# Sheet1_v12.net
KiCad netlist of a schematic drawn in Altium Designer
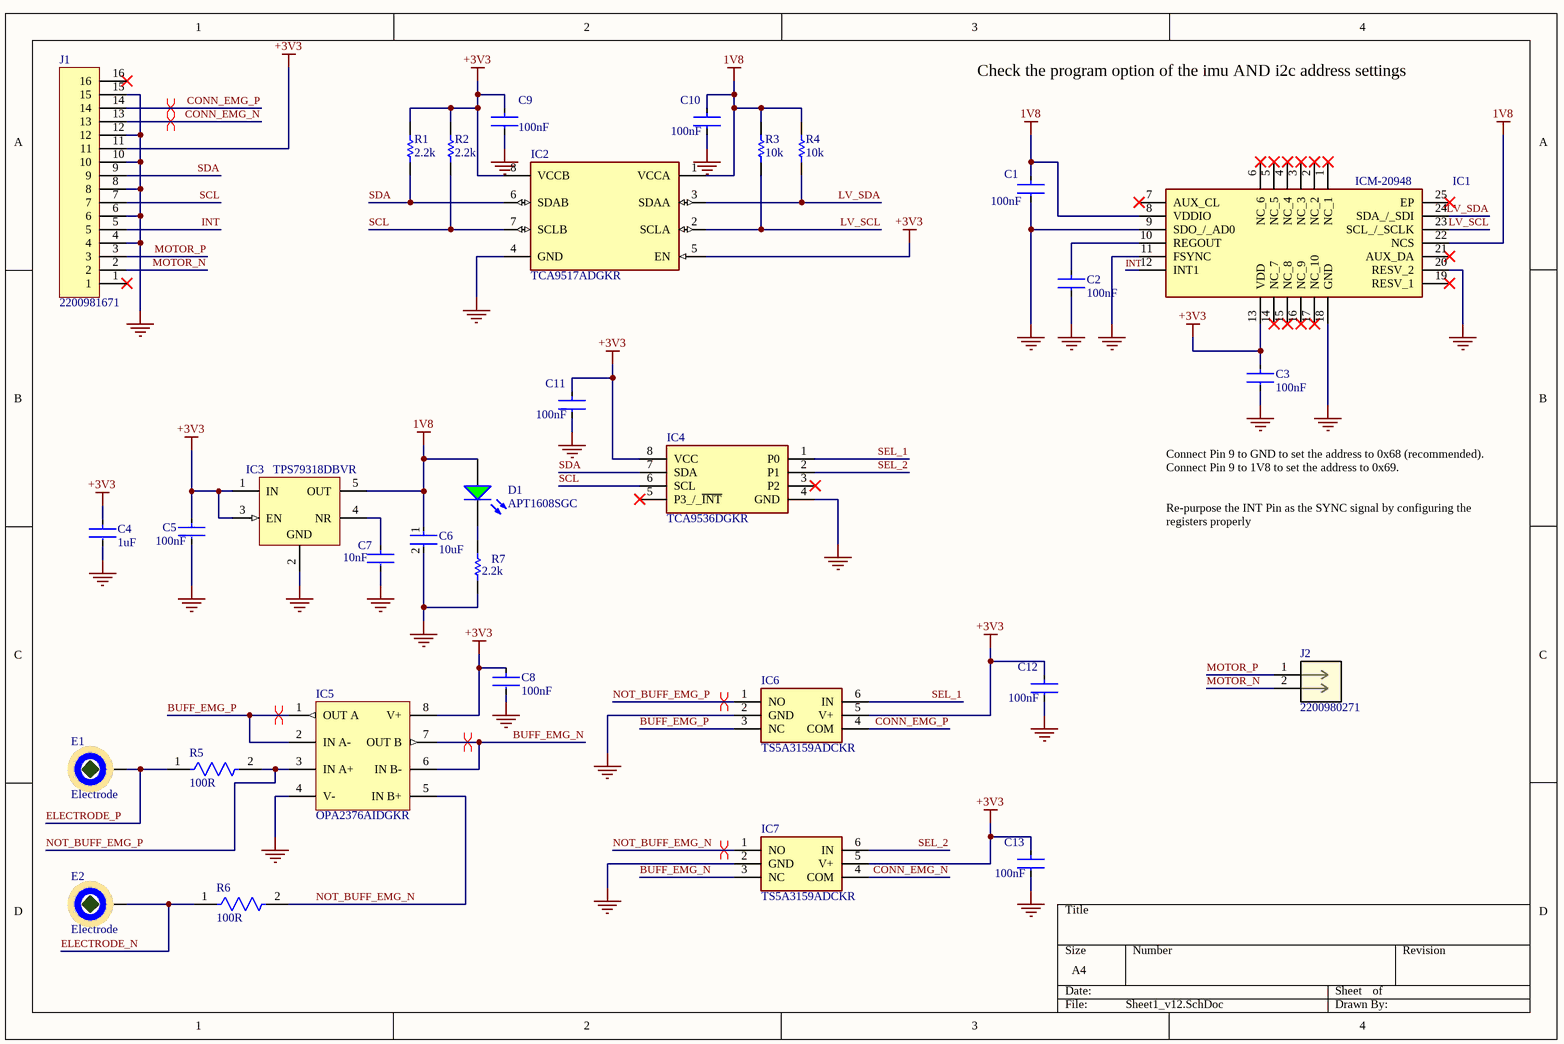
[diagram p0: Sheet1_v12.SchDoc]

(export (version "E")
  (design (tool "Eeschema 10.0.6"))
  (components
    (comp (ref "C1")
      (value "100nF")
      (footprint "FP-CC0603-DA-MFG")
      (description "100nF 50V X7R ±10% 0603 Multilayer Ceramic Capacitors MLCC - SMD/SMT ROHS")
      (fields (field (name "MANUFACTURER") "YAGEO") (field (name "VOLTAGE") "50 V"))
      (libsource (lib "Altium Content Vault") (part "11868f565c42a9108669ba33697ecf6"))
    )
    (comp (ref "C2")
      (value "100nF")
      (footprint "FP-CC0603-DA-MFG")
      (description "100nF 50V X7R ±10% 0603 Multilayer Ceramic Capacitors MLCC - SMD/SMT ROHS")
      (fields (field (name "MANUFACTURER") "YAGEO") (field (name "VOLTAGE") "50 V"))
      (libsource (lib "Altium Content Vault") (part "11868f565c42a9108669ba33697ecf6"))
    )
    (comp (ref "C3")
      (value "100nF")
      (footprint "FP-CC0603-DA-MFG")
      (description "100nF 50V X7R ±10% 0603 Multilayer Ceramic Capacitors MLCC - SMD/SMT ROHS")
      (fields (field (name "MANUFACTURER") "YAGEO") (field (name "VOLTAGE") "50 V"))
      (libsource (lib "Altium Content Vault") (part "11868f565c42a9108669ba33697ecf6"))
    )
    (comp (ref "C4")
      (value "1uF")
      (footprint "FP-C0402C-BB-IPC_B")
      (description "CAP CER 1UF 16V X5R 0402")
      (fields (field (name "TOLERANCE") "10%") (field (name "MPN") "C0402C105K4PACTU"))
      (libsource (lib "") (part "b4654b650e69147ec39a6b967a45e02_1"))
    )
    (comp (ref "C5")
      (value "100nF")
      (footprint "FP-GRM155-0_05-MFG")
      (description "Chip Multilayer Ceramic Capacitors for General Purpose, 0402, 0.10uF, X7S, 22%, 10%, 50V")
      (fields (field (name "TOLERANCE") "10%") (field (name "MPN") "GRM155C71H104KE19D"))
      (libsource (lib "Altium Content Vault") (part "02cd4be3c70576c341d710602a673aa"))
    )
    (comp (ref "C6")
      (value "10uF")
      (footprint "FP-GRM155-0_2-IPC_A")
      (description "Chip Multilayer Ceramic Capacitors for General Purpose, 0402, 10uF, X5R, 15%, 20%, 10V")
      (fields (field (name "MPN") "GRM155R61A106ME11D"))
      (libsource (lib "Altium Content Vault") (part "b4654b650e69147ec39a6b967a45e02"))
    )
    (comp (ref "C7")
      (value "10nF")
      (footprint "FP-C0402-BB-MFG")
      (description "C0402 10,000 pF X7R 10.00% 50 V")
      (fields
        (field (name "OCTOPART") "https://octopart.com/c0402c103k5rac7411-kemet-25528449")
        (field (name "TOLERANCE") "0.1")
      )
      (libsource (lib "") (part "b4654b650e69147ec39a6b967a45e02_1"))
    )
    (comp (ref "C8")
      (value "100nF")
      (footprint "FP-CC0603-DA-MFG")
      (description "100nF 50V X7R ±10% 0603 Multilayer Ceramic Capacitors MLCC - SMD/SMT ROHS")
      (fields (field (name "MANUFACTURER") "YAGEO") (field (name "VOLTAGE") "50 V"))
      (libsource (lib "Altium Content Vault") (part "11868f565c42a9108669ba33697ecf6"))
    )
    (comp (ref "C9")
      (value "100nF")
      (footprint "FP-GRM155-0_05-MFG")
      (description "Chip Multilayer Ceramic Capacitors for General Purpose, 0402, 0.10uF, X7S, 22%, 10%, 50V")
      (fields (field (name "TOLERANCE") "10%") (field (name "MPN") "GRM155C71H104KE19D"))
      (libsource (lib "Altium Content Vault") (part "02cd4be3c70576c341d710602a673aa"))
    )
    (comp (ref "C10")
      (value "100nF")
      (footprint "FP-GRM155-0_05-MFG")
      (description "Chip Multilayer Ceramic Capacitors for General Purpose, 0402, 0.10uF, X7S, 22%, 10%, 50V")
      (fields (field (name "TOLERANCE") "10%") (field (name "MPN") "GRM155C71H104KE19D"))
      (libsource (lib "Altium Content Vault") (part "02cd4be3c70576c341d710602a673aa"))
    )
    (comp (ref "C11")
      (value "100nF")
      (footprint "FP-GRM155-0_05-MFG")
      (description "Chip Multilayer Ceramic Capacitors for General Purpose, 0402, 0.10uF, X7S, 22%, 10%, 50V")
      (fields (field (name "TOLERANCE") "10%") (field (name "MPN") "GRM155C71H104KE19D"))
      (libsource (lib "Altium Content Vault") (part "02cd4be3c70576c341d710602a673aa"))
    )
    (comp (ref "C12")
      (value "100nF")
      (footprint "FP-GRM155-0_05-MFG")
      (description "Chip Multilayer Ceramic Capacitors for General Purpose, 0402, 0.10uF, X7S, 22%, 10%, 50V")
      (fields (field (name "TOLERANCE") "10%") (field (name "MPN") "GRM155C71H104KE19D"))
      (libsource (lib "Altium Content Vault") (part "02cd4be3c70576c341d710602a673aa"))
    )
    (comp (ref "C13")
      (value "100nF")
      (footprint "FP-GRM155-0_05-MFG")
      (description "Chip Multilayer Ceramic Capacitors for General Purpose, 0402, 0.10uF, X7S, 22%, 10%, 50V")
      (fields (field (name "TOLERANCE") "10%") (field (name "MPN") "GRM155C71H104KE19D"))
      (libsource (lib "Altium Content Vault") (part "02cd4be3c70576c341d710602a673aa"))
    )
    (comp (ref "D1")
      (value "APT1608SGC")
      (footprint "KING-APT1608SGC_V")
      (description "Super Bright Green LED, 62.5 mW, 25 mA, -40 to 85 degC, 2-Pin SMD, RoHS, Tape and Reel")
      (fields (field (name "MANUFACTURER") "Kingbright"))
      (libsource (lib "Altium Content Vault") (part "LED-GREEN-AK-2"))
    )
    (comp (ref "E1")
      (value "Electrode")
      (footprint "Electrode")
      (libsource (lib "Sensor_node") (part "Electrode"))
    )
    (comp (ref "E2")
      (value "Electrode")
      (footprint "Electrode")
      (libsource (lib "Sensor_node") (part "Electrode"))
    )
    (comp (ref "IC1")
      (value "ICM-20948")
      (footprint "SamacSys:QFN40P300X300X105-25N-D")
      (description "Integrated Circuit")
      (fields (field (name "MOUSER PART NUMBER") "410-ICM-20948"))
      (libsource (lib "*") (part "ICM-20948"))
    )
    (comp (ref "IC2")
      (value "TCA9517ADGKR")
      (footprint "FP-DGK0008A-IPC_C")
      (description "IC TRNSLTR BIDIRECTIONAL 8VSSOP")
      (libsource (lib "Altium Content Vault") (part "376f503177af6135b4bcb823927ec01"))
    )
    (comp (ref "IC3")
      (value "TPS79318DBVR")
      (footprint "DBV0005A_M")
      (fields (field (name "MANUFACTURER") "Texas Instruments"))
      (libsource (lib "Altium Content Vault") (part "TI-TPS79NXX-YYSOT5"))
    )
    (comp (ref "IC4")
      (value "TCA9536DGKR")
      (footprint "SamacSys:SOP65P490X110-8N")
      (description "Integrated Circuit")
      (fields (field (name "MOUSER PART NUMBER") "595-TCA9536DGKR"))
      (libsource (lib "*") (part "TCA9536DGKR"))
    )
    (comp (ref "IC5")
      (value "OPA2376AIDGKR")
      (footprint "OPA2376")
      (description "IC OPAMP GP 2 CIRCUIT 8VSSOP")
      (libsource (lib "Sensor_node") (part "OPA2376AIDGKR"))
    )
    (comp (ref "IC6")
      (value "TS5A3159ADCKR")
      (footprint "SamacSys:SOT65P210X110-6N")
      (description "IC SWITCH SPDTX1 900MOHM SC70-6")
      (fields (field (name "MOUSER PART NUMBER") "595-TS5A3159ADCKR"))
      (libsource (lib "*") (part "TS5A3159ADCKR"))
    )
    (comp (ref "IC7")
      (value "TS5A3159ADCKR")
      (footprint "SamacSys:SOT65P210X110-6N")
      (description "IC SWITCH SPDTX1 900MOHM SC70-6")
      (fields (field (name "MOUSER PART NUMBER") "595-TS5A3159ADCKR"))
      (libsource (lib "*") (part "TS5A3159ADCKR"))
    )
    (comp (ref "J1")
      (value "2200981671")
      (footprint "CONN_2200980000-SD_16_MOL")
      (description "Connector Header Through Hole, Right Angle 16 position 0.049\" (1.25mm)")
      (libsource (lib "Sensor_node") (part "2200981671"))
    )
    (comp (ref "J2")
      (value "2200980271")
      (footprint "2X1_right_angle_THT_CON")
      (description "Molex connector")
      (libsource (lib "Sensor_node") (part "2X1_RHTANG_HDR"))
    )
    (comp (ref "R1")
      (value "2.2k")
      (footprint "RESC0402(1005)_N")
      (description "2K2 0.063W 5% 0402 (1005 Metric)  SMD")
      (fields (field (name "TOLERANCE") "5 %") (field (name "POWER") "0.063 W"))
      (libsource (lib "Altium Content Vault") (part "RES"))
    )
    (comp (ref "R2")
      (value "2.2k")
      (footprint "RESC0402(1005)_N")
      (description "2K2 0.063W 5% 0402 (1005 Metric)  SMD")
      (fields (field (name "TOLERANCE") "5 %") (field (name "POWER") "0.063 W"))
      (libsource (lib "Altium Content Vault") (part "RES"))
    )
    (comp (ref "R3")
      (value "10k")
      (footprint "RESC1005X40X20NL05T10")
      (fields
        (field (name "MANUFACTURER") "Vishay BCcomponents")
        (field (name "PART NUMBER") "TNPW040210K0DEED")
      )
      (libsource (lib "Altium Content Vault") (part "RES"))
    )
    (comp (ref "R4")
      (value "10k")
      (footprint "RESC1005X40X20NL05T10")
      (fields
        (field (name "MANUFACTURER") "Vishay BCcomponents")
        (field (name "PART NUMBER") "TNPW040210K0DEED")
      )
      (libsource (lib "Altium Content Vault") (part "RES"))
    )
    (comp (ref "R5")
      (value "100R")
      (footprint "FP-MCS0402-IPC_B")
      (description "RES SMD 1.2K OHM 1% 1/10W 0402")
      (fields (field (name "TOLERANCE") "0.5%") (field (name "MPN") "MCS0402MD1000DE000"))
      (libsource (lib "Altium Content Vault") (part "1029c3af85768c4190bb7ad29bc67b5"))
    )
    (comp (ref "R6")
      (value "100R")
      (footprint "FP-MCS0402-IPC_B")
      (description "RES SMD 1.2K OHM 1% 1/10W 0402")
      (fields (field (name "TOLERANCE") "0.5%") (field (name "MPN") "MCS0402MD1000DE000"))
      (libsource (lib "Altium Content Vault") (part "1029c3af85768c4190bb7ad29bc67b5"))
    )
    (comp (ref "R7")
      (value "2.2k")
      (footprint "RESC0402(1005)_N")
      (description "2K2 0.063W 5% 0402 (1005 Metric)  SMD")
      (fields (field (name "TOLERANCE") "5 %") (field (name "POWER") "0.063 W"))
      (libsource (lib "Altium Content Vault") (part "RES"))
    )
  )
  (nets
    (net (code "1") (name "+3V3") (class "Default")
      (node (ref "C11") (pin "1") (pinfunction "1_1") (pintype "passive"))
      (node (ref "C12") (pin "1") (pinfunction "1_1") (pintype "passive"))
      (node (ref "C13") (pin "1") (pinfunction "1_1") (pintype "passive"))
      (node (ref "C3") (pin "1") (pinfunction "1_1") (pintype "passive"))
      (node (ref "C4") (pin "1") (pinfunction "1_1") (pintype "passive"))
      (node (ref "C5") (pin "1") (pinfunction "1_1") (pintype "passive"))
      (node (ref "C8") (pin "1") (pinfunction "1_1") (pintype "passive"))
      (node (ref "C9") (pin "1") (pinfunction "1_1") (pintype "passive"))
      (node (ref "IC1") (pin "13") (pinfunction "VDD_13") (pintype "passive"))
      (node (ref "IC2") (pin "5") (pinfunction "EN_5") (pintype "input"))
      (node (ref "IC2") (pin "8") (pinfunction "VCCB_8") (pintype "power_in"))
      (node (ref "IC3") (pin "1") (pinfunction "IN_1") (pintype "power_in"))
      (node (ref "IC3") (pin "3") (pinfunction "EN_3") (pintype "input"))
      (node (ref "IC4") (pin "8") (pinfunction "VCC_8") (pintype "passive"))
      (node (ref "IC5") (pin "8") (pinfunction "V+_8") (pintype "power_in"))
      (node (ref "IC6") (pin "5") (pinfunction "V+_5") (pintype "passive"))
      (node (ref "IC7") (pin "5") (pinfunction "V+_5") (pintype "passive"))
      (node (ref "J1") (pin "11") (pinfunction "11_11") (pintype "passive"))
      (node (ref "R1") (pin "2") (pinfunction "2_2") (pintype "passive"))
      (node (ref "R2") (pin "2") (pinfunction "2_2") (pintype "passive"))
    )
    (net (code "2") (name "/BUFF_EMG_N") (class "Default")
      (node (ref "IC5") (pin "6") (pinfunction "IN_B-_6") (pintype "passive"))
      (node (ref "IC5") (pin "7") (pinfunction "OUT_B_7") (pintype "output"))
      (node (ref "IC7") (pin "3") (pinfunction "NC_3") (pintype "passive"))
    )
    (net (code "3") (name "/BUFF_EMG_P") (class "Default")
      (node (ref "IC5") (pin "1") (pinfunction "OUT_A_1") (pintype "output"))
      (node (ref "IC5") (pin "2") (pinfunction "IN_A-_2") (pintype "passive"))
      (node (ref "IC6") (pin "3") (pinfunction "NC_3") (pintype "passive"))
    )
    (net (code "4") (name "/CONN_EMG_N") (class "Default")
      (node (ref "IC7") (pin "4") (pinfunction "COM_4") (pintype "passive"))
      (node (ref "J1") (pin "13") (pinfunction "13_13") (pintype "passive"))
    )
    (net (code "5") (name "/CONN_EMG_P") (class "Default")
      (node (ref "IC6") (pin "4") (pinfunction "COM_4") (pintype "passive"))
      (node (ref "J1") (pin "14") (pinfunction "14_14") (pintype "passive"))
    )
    (net (code "6") (name "/ELECTRODE_N") (class "Default")
      (node (ref "E2") (pin "1") (pinfunction "1_1") (pintype "passive"))
      (node (ref "R6") (pin "1") (pinfunction "1_1") (pintype "passive"))
    )
    (net (code "7") (name "/ELECTRODE_P") (class "Default")
      (node (ref "E1") (pin "1") (pinfunction "1_1") (pintype "passive"))
      (node (ref "R5") (pin "1") (pinfunction "1_1") (pintype "passive"))
    )
    (net (code "8") (name "/INT") (class "Default")
      (node (ref "IC1") (pin "12") (pinfunction "INT1_12") (pintype "passive"))
      (node (ref "J1") (pin "5") (pinfunction "5_5") (pintype "passive"))
    )
    (net (code "9") (name "/LV_SCL") (class "Default")
      (node (ref "IC1") (pin "23") (pinfunction "SCL_/_SCLK_23") (pintype "passive"))
      (node (ref "IC2") (pin "2") (pinfunction "SCLA_2") (pintype "bidirectional"))
      (node (ref "R3") (pin "1") (pinfunction "1_1") (pintype "passive"))
    )
    (net (code "10") (name "/LV_SDA") (class "Default")
      (node (ref "IC1") (pin "24") (pinfunction "SDA_/_SDI_24") (pintype "passive"))
      (node (ref "IC2") (pin "3") (pinfunction "SDAA_3") (pintype "bidirectional"))
      (node (ref "R4") (pin "1") (pinfunction "1_1") (pintype "passive"))
    )
    (net (code "11") (name "/MOTOR_N") (class "Default")
      (node (ref "J1") (pin "2") (pinfunction "2_2") (pintype "passive"))
      (node (ref "J2") (pin "2") (pinfunction "2_2") (pintype "passive"))
    )
    (net (code "12") (name "/MOTOR_P") (class "Default")
      (node (ref "J1") (pin "3") (pinfunction "3_3") (pintype "passive"))
      (node (ref "J2") (pin "1") (pinfunction "1_1") (pintype "passive"))
    )
    (net (code "13") (name "/NOT_BUFF_EMG_N") (class "Default")
      (node (ref "IC5") (pin "5") (pinfunction "IN_B+_5") (pintype "passive"))
      (node (ref "IC7") (pin "1") (pinfunction "NO_1") (pintype "passive"))
      (node (ref "R6") (pin "2") (pinfunction "2_2") (pintype "passive"))
    )
    (net (code "14") (name "/NOT_BUFF_EMG_P") (class "Default")
      (node (ref "IC5") (pin "3") (pinfunction "IN_A+_3") (pintype "passive"))
      (node (ref "IC6") (pin "1") (pinfunction "NO_1") (pintype "passive"))
      (node (ref "R5") (pin "2") (pinfunction "2_2") (pintype "passive"))
    )
    (net (code "15") (name "/SCL") (class "Default")
      (node (ref "IC2") (pin "7") (pinfunction "SCLB_7") (pintype "bidirectional"))
      (node (ref "IC4") (pin "6") (pinfunction "SCL_6") (pintype "passive"))
      (node (ref "J1") (pin "7") (pinfunction "7_7") (pintype "passive"))
      (node (ref "R2") (pin "1") (pinfunction "1_1") (pintype "passive"))
    )
    (net (code "16") (name "/SDA") (class "Default")
      (node (ref "IC2") (pin "6") (pinfunction "SDAB_6") (pintype "bidirectional"))
      (node (ref "IC4") (pin "7") (pinfunction "SDA_7") (pintype "passive"))
      (node (ref "J1") (pin "9") (pinfunction "9_9") (pintype "passive"))
      (node (ref "R1") (pin "1") (pinfunction "1_1") (pintype "passive"))
    )
    (net (code "17") (name "/SEL_1") (class "Default")
      (node (ref "IC4") (pin "1") (pinfunction "P0_1") (pintype "passive"))
      (node (ref "IC6") (pin "6") (pinfunction "IN_6") (pintype "passive"))
    )
    (net (code "18") (name "/SEL_2") (class "Default")
      (node (ref "IC4") (pin "2") (pinfunction "P1_2") (pintype "passive"))
      (node (ref "IC7") (pin "6") (pinfunction "IN_6") (pintype "passive"))
    )
    (net (code "19") (name "1V8") (class "Default")
      (node (ref "C1") (pin "1") (pinfunction "1_1") (pintype "passive"))
      (node (ref "C10") (pin "1") (pinfunction "1_1") (pintype "passive"))
      (node (ref "C6") (pin "1") (pinfunction "1_1") (pintype "passive"))
      (node (ref "D1") (pin "1") (pinfunction "A_1") (pintype "passive"))
      (node (ref "IC1") (pin "22") (pinfunction "NCS_22") (pintype "passive"))
      (node (ref "IC1") (pin "8") (pinfunction "VDDIO_8") (pintype "passive"))
      (node (ref "IC2") (pin "1") (pinfunction "VCCA_1") (pintype "power_in"))
      (node (ref "IC3") (pin "5") (pinfunction "OUT_5") (pintype "power_in"))
      (node (ref "R3") (pin "2") (pinfunction "2_2") (pintype "passive"))
      (node (ref "R4") (pin "2") (pinfunction "2_2") (pintype "passive"))
    )
    (net (code "20") (name "GND") (class "Default")
      (node (ref "C1") (pin "2") (pinfunction "2_2") (pintype "passive"))
      (node (ref "C10") (pin "2") (pinfunction "2_2") (pintype "passive"))
      (node (ref "C11") (pin "2") (pinfunction "2_2") (pintype "passive"))
      (node (ref "C12") (pin "2") (pinfunction "2_2") (pintype "passive"))
      (node (ref "C13") (pin "2") (pinfunction "2_2") (pintype "passive"))
      (node (ref "C2") (pin "2") (pinfunction "2_2") (pintype "passive"))
      (node (ref "C3") (pin "2") (pinfunction "2_2") (pintype "passive"))
      (node (ref "C4") (pin "2") (pinfunction "2_2") (pintype "passive"))
      (node (ref "C5") (pin "2") (pinfunction "2_2") (pintype "passive"))
      (node (ref "C6") (pin "2") (pinfunction "2_2") (pintype "passive"))
      (node (ref "C7") (pin "2") (pinfunction "2_2") (pintype "passive"))
      (node (ref "C8") (pin "2") (pinfunction "2_2") (pintype "passive"))
      (node (ref "C9") (pin "2") (pinfunction "2_2") (pintype "passive"))
      (node (ref "IC1") (pin "11") (pinfunction "FSYNC_11") (pintype "passive"))
      (node (ref "IC1") (pin "18") (pinfunction "GND_18") (pintype "passive"))
      (node (ref "IC1") (pin "20") (pinfunction "RESV_2_20") (pintype "passive"))
      (node (ref "IC1") (pin "9") (pinfunction "SDO_/_AD0_9") (pintype "passive"))
      (node (ref "IC2") (pin "4") (pinfunction "GND_4") (pintype "power_in"))
      (node (ref "IC3") (pin "2") (pinfunction "GND_2") (pintype "power_in"))
      (node (ref "IC4") (pin "4") (pinfunction "GND_4") (pintype "passive"))
      (node (ref "IC5") (pin "4") (pinfunction "V-_4") (pintype "power_in"))
      (node (ref "IC6") (pin "2") (pinfunction "GND_2") (pintype "passive"))
      (node (ref "IC7") (pin "2") (pinfunction "GND_2") (pintype "passive"))
      (node (ref "J1") (pin "10") (pinfunction "10_10") (pintype "passive"))
      (node (ref "J1") (pin "12") (pinfunction "12_12") (pintype "passive"))
      (node (ref "J1") (pin "15") (pinfunction "15_15") (pintype "passive"))
      (node (ref "J1") (pin "4") (pinfunction "4_4") (pintype "passive"))
      (node (ref "J1") (pin "6") (pinfunction "6_6") (pintype "passive"))
      (node (ref "J1") (pin "8") (pinfunction "8_8") (pintype "passive"))
      (node (ref "R7") (pin "1") (pinfunction "1_1") (pintype "passive"))
    )
    (net (code "21") (name "Net-(D1-K)") (class "Default")
      (node (ref "D1") (pin "2") (pinfunction "K_2") (pintype "passive"))
      (node (ref "R7") (pin "2") (pinfunction "2_2") (pintype "passive"))
    )
    (net (code "22") (name "Net-(IC1-REGOUT)") (class "Default")
      (node (ref "C2") (pin "1") (pinfunction "1_1") (pintype "passive"))
      (node (ref "IC1") (pin "10") (pinfunction "REGOUT_10") (pintype "passive"))
    )
    (net (code "23") (name "Net-(IC3-NR)") (class "Default")
      (node (ref "C7") (pin "1") (pinfunction "1_1") (pintype "passive"))
      (node (ref "IC3") (pin "4") (pinfunction "NR_4") (pintype "passive"))
    )
    (net (code "24") (name "unconnected-(IC1-AUX_CL-Pad7)") (class "Default")
      (node (ref "IC1") (pin "7") (pinfunction "AUX_CL_7") (pintype "passive+no_connect"))
    )
    (net (code "25") (name "unconnected-(IC1-AUX_DA-Pad21)") (class "Default")
      (node (ref "IC1") (pin "21") (pinfunction "AUX_DA_21") (pintype "passive+no_connect"))
    )
    (net (code "26") (name "unconnected-(IC1-EP-Pad25)") (class "Default")
      (node (ref "IC1") (pin "25") (pinfunction "EP_25") (pintype "passive+no_connect"))
    )
    (net (code "27") (name "unconnected-(IC1-NC_1-Pad1)") (class "Default")
      (node (ref "IC1") (pin "1") (pinfunction "NC_1_1") (pintype "passive+no_connect"))
    )
    (net (code "28") (name "unconnected-(IC1-NC_2-Pad2)") (class "Default")
      (node (ref "IC1") (pin "2") (pinfunction "NC_2_2") (pintype "passive+no_connect"))
    )
    (net (code "29") (name "unconnected-(IC1-NC_3-Pad3)") (class "Default")
      (node (ref "IC1") (pin "3") (pinfunction "NC_3_3") (pintype "passive+no_connect"))
    )
    (net (code "30") (name "unconnected-(IC1-NC_4-Pad4)") (class "Default")
      (node (ref "IC1") (pin "4") (pinfunction "NC_4_4") (pintype "passive+no_connect"))
    )
    (net (code "31") (name "unconnected-(IC1-NC_5-Pad5)") (class "Default")
      (node (ref "IC1") (pin "5") (pinfunction "NC_5_5") (pintype "passive+no_connect"))
    )
    (net (code "32") (name "unconnected-(IC1-NC_6-Pad6)") (class "Default")
      (node (ref "IC1") (pin "6") (pinfunction "NC_6_6") (pintype "passive+no_connect"))
    )
    (net (code "33") (name "unconnected-(IC1-NC_7-Pad14)") (class "Default")
      (node (ref "IC1") (pin "14") (pinfunction "NC_7_14") (pintype "passive+no_connect"))
    )
    (net (code "34") (name "unconnected-(IC1-NC_8-Pad15)") (class "Default")
      (node (ref "IC1") (pin "15") (pinfunction "NC_8_15") (pintype "passive+no_connect"))
    )
    (net (code "35") (name "unconnected-(IC1-NC_9-Pad16)") (class "Default")
      (node (ref "IC1") (pin "16") (pinfunction "NC_9_16") (pintype "passive+no_connect"))
    )
    (net (code "36") (name "unconnected-(IC1-NC_10-Pad17)") (class "Default")
      (node (ref "IC1") (pin "17") (pinfunction "NC_10_17") (pintype "passive+no_connect"))
    )
    (net (code "37") (name "unconnected-(IC1-RESV_1-Pad19)") (class "Default")
      (node (ref "IC1") (pin "19") (pinfunction "RESV_1_19") (pintype "passive+no_connect"))
    )
    (net (code "38") (name "unconnected-(IC4-P2-Pad3)") (class "Default")
      (node (ref "IC4") (pin "3") (pinfunction "P2_3") (pintype "passive+no_connect"))
    )
    (net (code "39") (name "unconnected-(IC4-P3_{slash}_~{INT}-Pad5)") (class "Default")
      (node (ref "IC4") (pin "5") (pinfunction "P3_/_~{INT}_5") (pintype "passive+no_connect"))
    )
    (net (code "40") (name "unconnected-(J1-Pad1)") (class "Default")
      (node (ref "J1") (pin "1") (pinfunction "1_1") (pintype "passive+no_connect"))
    )
    (net (code "41") (name "unconnected-(J1-Pad16)") (class "Default")
      (node (ref "J1") (pin "16") (pinfunction "16_16") (pintype "passive+no_connect"))
    )
  )
)
